# Nusbio_2_-_IC2_Extension.net
KiCad netlist of a schematic drawn in EAGLE
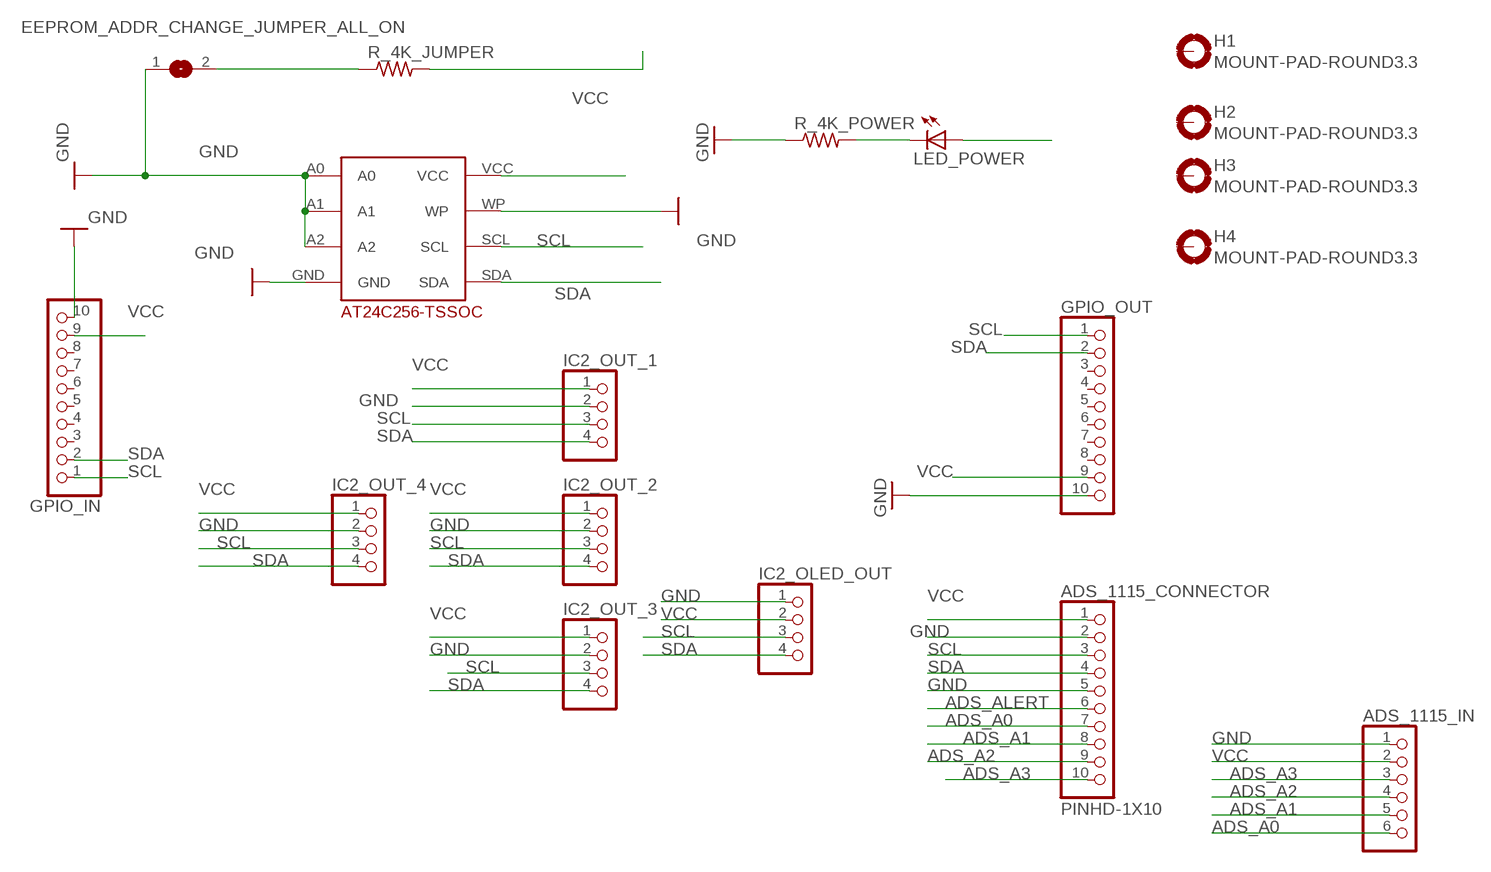
[diagram p0: schematic, sheet 1]

(export (version "E")
  (design (tool "Eeschema 10.0.6"))
  (components
    (comp (ref "ADS_1115_CONNECTOR")
      (value "PINHD-1X10")
      (footprint "eagle-import:1X10-BIG")
      (libsource (lib "eagle-import") (part "PINHD-1X10"))
    )
    (comp (ref "ADS_1115_IN")
      (value "PINHD-1X6")
      (footprint "eagle-import:1X06")
      (libsource (lib "eagle-import") (part "PINHD-1X6"))
    )
    (comp (ref "EEPROM_ADDR_CHANGE_JUMPER_ALL_ON")
      (value "SOLDERJUMPERREFLOW")
      (footprint "eagle-import:SOLDERJUMPER_REFLOW")
      (libsource (lib "eagle-import") (part "SOLDERJUMPERREFLOW"))
    )
    (comp (ref "EEPROM_AT24C256")
      (value "DECADE-AT24C256-10TI-2.7")
      (footprint "eagle-import:DECADE-AT24CXX")
      (libsource (lib "eagle-import") (part "DECADE-AT24C256-10TI-2.7"))
    )
    (comp (ref "GPIO_IN")
      (value "PINHD-1X10")
      (footprint "eagle-import:1X10-BIG")
      (libsource (lib "eagle-import") (part "PINHD-1X10"))
    )
    (comp (ref "GPIO_OUT")
      (value "PINHD-1X10")
      (footprint "eagle-import:1X10-BIG")
      (libsource (lib "eagle-import") (part "PINHD-1X10"))
    )
    (comp (ref "H1")
      (value "MOUNT-PAD-ROUND3.3")
      (footprint "eagle-import:3,3-PAD")
      (libsource (lib "eagle-import") (part "MOUNT-PAD-ROUND3.3"))
    )
    (comp (ref "H2")
      (value "MOUNT-PAD-ROUND3.3")
      (footprint "eagle-import:3,3-PAD")
      (libsource (lib "eagle-import") (part "MOUNT-PAD-ROUND3.3"))
    )
    (comp (ref "H3")
      (value "MOUNT-PAD-ROUND3.3")
      (footprint "eagle-import:3,3-PAD")
      (libsource (lib "eagle-import") (part "MOUNT-PAD-ROUND3.3"))
    )
    (comp (ref "H4")
      (value "MOUNT-PAD-ROUND3.3")
      (footprint "eagle-import:3,3-PAD")
      (libsource (lib "eagle-import") (part "MOUNT-PAD-ROUND3.3"))
    )
    (comp (ref "IC2_OLED_OUT")
      (value "PINHD-1X4")
      (footprint "eagle-import:1X04")
      (libsource (lib "eagle-import") (part "PINHD-1X4"))
    )
    (comp (ref "IC2_OUT_1")
      (value "PINHD-1X4")
      (footprint "eagle-import:1X04")
      (libsource (lib "eagle-import") (part "PINHD-1X4"))
    )
    (comp (ref "IC2_OUT_2")
      (value "PINHD-1X4")
      (footprint "eagle-import:1X04")
      (libsource (lib "eagle-import") (part "PINHD-1X4"))
    )
    (comp (ref "IC2_OUT_3")
      (value "PINHD-1X4")
      (footprint "eagle-import:1X04")
      (libsource (lib "eagle-import") (part "PINHD-1X4"))
    )
    (comp (ref "IC2_OUT_4")
      (value "PINHD-1X4")
      (footprint "eagle-import:1X04")
      (libsource (lib "eagle-import") (part "PINHD-1X4"))
    )
    (comp (ref "LED_POWER")
      (value "LEDSMT1206")
      (footprint "eagle-import:1206")
      (libsource (lib "eagle-import") (part "LEDSMT1206"))
    )
    (comp (ref "R_4K_JUMPER")
      (value "R-US_R1206")
      (footprint "eagle-import:R1206")
      (libsource (lib "eagle-import") (part "R-US_R1206"))
    )
    (comp (ref "R_4K_POWER")
      (value "R-US_R1206")
      (footprint "eagle-import:R1206")
      (libsource (lib "eagle-import") (part "R-US_R1206"))
    )
  )
  (nets
    (net (code "1") (name "/ADS_A0") (class "Default")
      (node (ref "ADS_1115_CONNECTOR") (pin "7") (pinfunction "7_7") (pintype "passive"))
      (node (ref "ADS_1115_IN") (pin "6") (pinfunction "6_6") (pintype "passive"))
    )
    (net (code "2") (name "/ADS_A1") (class "Default")
      (node (ref "ADS_1115_CONNECTOR") (pin "8") (pinfunction "8_8") (pintype "passive"))
      (node (ref "ADS_1115_IN") (pin "5") (pinfunction "5_5") (pintype "passive"))
    )
    (net (code "3") (name "/ADS_A2") (class "Default")
      (node (ref "ADS_1115_CONNECTOR") (pin "9") (pinfunction "9_9") (pintype "passive"))
      (node (ref "ADS_1115_IN") (pin "4") (pinfunction "4_4") (pintype "passive"))
    )
    (net (code "4") (name "/ADS_A3") (class "Default")
      (node (ref "ADS_1115_CONNECTOR") (pin "10") (pinfunction "10_10") (pintype "passive"))
      (node (ref "ADS_1115_IN") (pin "3") (pinfunction "3_3") (pintype "passive"))
    )
    (net (code "5") (name "/ADS_ALERT") (class "Default")
      (node (ref "ADS_1115_CONNECTOR") (pin "6") (pinfunction "6_6") (pintype "passive"))
    )
    (net (code "6") (name "/SCL") (class "Default")
      (node (ref "ADS_1115_CONNECTOR") (pin "3") (pinfunction "3_3") (pintype "passive"))
      (node (ref "EEPROM_AT24C256") (pin "SCL") (pinfunction "SCL_SCL") (pintype "bidirectional"))
      (node (ref "GPIO_IN") (pin "1") (pinfunction "1_1") (pintype "passive"))
      (node (ref "GPIO_OUT") (pin "1") (pinfunction "1_1") (pintype "passive"))
      (node (ref "IC2_OLED_OUT") (pin "3") (pinfunction "3_3") (pintype "passive"))
      (node (ref "IC2_OUT_1") (pin "3") (pinfunction "3_3") (pintype "passive"))
      (node (ref "IC2_OUT_2") (pin "3") (pinfunction "3_3") (pintype "passive"))
      (node (ref "IC2_OUT_3") (pin "3") (pinfunction "3_3") (pintype "passive"))
      (node (ref "IC2_OUT_4") (pin "3") (pinfunction "3_3") (pintype "passive"))
    )
    (net (code "7") (name "/SDA") (class "Default")
      (node (ref "ADS_1115_CONNECTOR") (pin "4") (pinfunction "4_4") (pintype "passive"))
      (node (ref "EEPROM_AT24C256") (pin "SDA") (pinfunction "SDA_SDA") (pintype "bidirectional"))
      (node (ref "GPIO_IN") (pin "2") (pinfunction "2_2") (pintype "passive"))
      (node (ref "GPIO_OUT") (pin "2") (pinfunction "2_2") (pintype "passive"))
      (node (ref "IC2_OLED_OUT") (pin "4") (pinfunction "4_4") (pintype "passive"))
      (node (ref "IC2_OUT_1") (pin "4") (pinfunction "4_4") (pintype "passive"))
      (node (ref "IC2_OUT_2") (pin "4") (pinfunction "4_4") (pintype "passive"))
      (node (ref "IC2_OUT_3") (pin "4") (pinfunction "4_4") (pintype "passive"))
      (node (ref "IC2_OUT_4") (pin "4") (pinfunction "4_4") (pintype "passive"))
    )
    (net (code "8") (name "/VCC") (class "Default")
      (node (ref "ADS_1115_CONNECTOR") (pin "1") (pinfunction "1_1") (pintype "passive"))
      (node (ref "ADS_1115_IN") (pin "2") (pinfunction "2_2") (pintype "passive"))
      (node (ref "GPIO_IN") (pin "9") (pinfunction "9_9") (pintype "passive"))
      (node (ref "GPIO_OUT") (pin "9") (pinfunction "9_9") (pintype "passive"))
      (node (ref "IC2_OLED_OUT") (pin "2") (pinfunction "2_2") (pintype "passive"))
      (node (ref "IC2_OUT_1") (pin "1") (pinfunction "1_1") (pintype "passive"))
      (node (ref "IC2_OUT_2") (pin "1") (pinfunction "1_1") (pintype "passive"))
      (node (ref "IC2_OUT_3") (pin "1") (pinfunction "1_1") (pintype "passive"))
      (node (ref "IC2_OUT_4") (pin "1") (pinfunction "1_1") (pintype "passive"))
      (node (ref "LED_POWER") (pin "A") (pinfunction "A_A") (pintype "passive"))
      (node (ref "R_4K_JUMPER") (pin "2") (pinfunction "2_2") (pintype "passive"))
    )
    (net (code "9") (name "GND") (class "Default")
      (node (ref "ADS_1115_CONNECTOR") (pin "2") (pinfunction "2_2") (pintype "passive"))
      (node (ref "ADS_1115_CONNECTOR") (pin "5") (pinfunction "5_5") (pintype "passive"))
      (node (ref "ADS_1115_IN") (pin "1") (pinfunction "1_1") (pintype "passive"))
      (node (ref "EEPROM_ADDR_CHANGE_JUMPER_ALL_ON") (pin "1") (pinfunction "1_1") (pintype "passive"))
      (node (ref "EEPROM_AT24C256") (pin "A0") (pinfunction "A0_A0") (pintype "bidirectional"))
      (node (ref "EEPROM_AT24C256") (pin "A1") (pinfunction "A1_A1") (pintype "bidirectional"))
      (node (ref "EEPROM_AT24C256") (pin "A2") (pinfunction "A2_A2") (pintype "bidirectional"))
      (node (ref "EEPROM_AT24C256") (pin "GND") (pinfunction "GND_GND") (pintype "bidirectional"))
      (node (ref "EEPROM_AT24C256") (pin "WP") (pinfunction "WP_WP") (pintype "bidirectional"))
      (node (ref "GPIO_IN") (pin "10") (pinfunction "10_10") (pintype "passive"))
      (node (ref "GPIO_OUT") (pin "10") (pinfunction "10_10") (pintype "passive"))
      (node (ref "IC2_OLED_OUT") (pin "1") (pinfunction "1_1") (pintype "passive"))
      (node (ref "IC2_OUT_1") (pin "2") (pinfunction "2_2") (pintype "passive"))
      (node (ref "IC2_OUT_2") (pin "2") (pinfunction "2_2") (pintype "passive"))
      (node (ref "IC2_OUT_3") (pin "2") (pinfunction "2_2") (pintype "passive"))
      (node (ref "IC2_OUT_4") (pin "2") (pinfunction "2_2") (pintype "passive"))
      (node (ref "R_4K_POWER") (pin "1") (pinfunction "1_1") (pintype "passive"))
    )
    (net (code "10") (name "Net-(EEPROM_ADDR_CHANGE_JUMPER_ALL_ON-Pad2)") (class "Default")
      (node (ref "EEPROM_ADDR_CHANGE_JUMPER_ALL_ON") (pin "2") (pinfunction "2_2") (pintype "passive"))
      (node (ref "R_4K_JUMPER") (pin "1") (pinfunction "1_1") (pintype "passive"))
    )
    (net (code "11") (name "Net-(LED_POWER-PadC)") (class "Default")
      (node (ref "LED_POWER") (pin "C") (pinfunction "C_C") (pintype "passive"))
      (node (ref "R_4K_POWER") (pin "2") (pinfunction "2_2") (pintype "passive"))
    )
    (net (code "12") (name "unconnected-(EEPROM_AT24C256-PadVCC)") (class "Default")
      (node (ref "EEPROM_AT24C256") (pin "VCC") (pinfunction "VCC_VCC") (pintype "bidirectional"))
    )
    (net (code "13") (name "unconnected-(GPIO_IN-Pad3)") (class "Default")
      (node (ref "GPIO_IN") (pin "3") (pinfunction "3_3") (pintype "passive"))
    )
    (net (code "14") (name "unconnected-(GPIO_IN-Pad4)") (class "Default")
      (node (ref "GPIO_IN") (pin "4") (pinfunction "4_4") (pintype "passive"))
    )
    (net (code "15") (name "unconnected-(GPIO_IN-Pad5)") (class "Default")
      (node (ref "GPIO_IN") (pin "5") (pinfunction "5_5") (pintype "passive"))
    )
    (net (code "16") (name "unconnected-(GPIO_IN-Pad6)") (class "Default")
      (node (ref "GPIO_IN") (pin "6") (pinfunction "6_6") (pintype "passive"))
    )
    (net (code "17") (name "unconnected-(GPIO_IN-Pad7)") (class "Default")
      (node (ref "GPIO_IN") (pin "7") (pinfunction "7_7") (pintype "passive"))
    )
    (net (code "18") (name "unconnected-(GPIO_IN-Pad8)") (class "Default")
      (node (ref "GPIO_IN") (pin "8") (pinfunction "8_8") (pintype "passive"))
    )
    (net (code "19") (name "unconnected-(GPIO_OUT-Pad3)") (class "Default")
      (node (ref "GPIO_OUT") (pin "3") (pinfunction "3_3") (pintype "passive"))
    )
    (net (code "20") (name "unconnected-(GPIO_OUT-Pad4)") (class "Default")
      (node (ref "GPIO_OUT") (pin "4") (pinfunction "4_4") (pintype "passive"))
    )
    (net (code "21") (name "unconnected-(GPIO_OUT-Pad5)") (class "Default")
      (node (ref "GPIO_OUT") (pin "5") (pinfunction "5_5") (pintype "passive"))
    )
    (net (code "22") (name "unconnected-(GPIO_OUT-Pad6)") (class "Default")
      (node (ref "GPIO_OUT") (pin "6") (pinfunction "6_6") (pintype "passive"))
    )
    (net (code "23") (name "unconnected-(GPIO_OUT-Pad7)") (class "Default")
      (node (ref "GPIO_OUT") (pin "7") (pinfunction "7_7") (pintype "passive"))
    )
    (net (code "24") (name "unconnected-(GPIO_OUT-Pad8)") (class "Default")
      (node (ref "GPIO_OUT") (pin "8") (pinfunction "8_8") (pintype "passive"))
    )
    (net (code "25") (name "unconnected-(H1-MOUNT-PadB3,3)") (class "Default")
      (node (ref "H1") (pin "B3,3") (pinfunction "MOUNT_B3,3") (pintype "passive"))
    )
    (net (code "26") (name "unconnected-(H2-MOUNT-PadB3,3)") (class "Default")
      (node (ref "H2") (pin "B3,3") (pinfunction "MOUNT_B3,3") (pintype "passive"))
    )
    (net (code "27") (name "unconnected-(H3-MOUNT-PadB3,3)") (class "Default")
      (node (ref "H3") (pin "B3,3") (pinfunction "MOUNT_B3,3") (pintype "passive"))
    )
    (net (code "28") (name "unconnected-(H4-MOUNT-PadB3,3)") (class "Default")
      (node (ref "H4") (pin "B3,3") (pinfunction "MOUNT_B3,3") (pintype "passive"))
    )
  )
)
